# power_supply.net
KiCad netlist of a schematic drawn in EAGLE
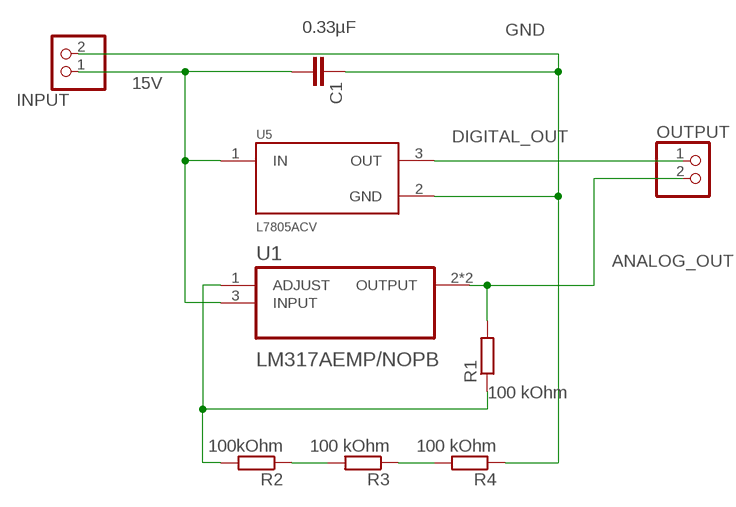
[diagram p0: schematic, sheet 1]

(export (version "E")
  (design (tool "Eeschema 10.0.6"))
  (components
    (comp (ref "C1")
      (value "0.33µF")
      (footprint "eagle-import:C0805")
      (libsource (lib "eagle-import") (part "C-EUC0805"))
    )
    (comp (ref "INPUT")
      (value "PINHD-1X2")
      (footprint "eagle-import:1X02")
      (libsource (lib "eagle-import") (part "PINHD-1X2"))
    )
    (comp (ref "OUTPUT")
      (value "PINHD-1X2")
      (footprint "eagle-import:1X02")
      (libsource (lib "eagle-import") (part "PINHD-1X2"))
    )
    (comp (ref "R1")
      (value "100 kOhm")
      (footprint "eagle-import:R0805")
      (libsource (lib "eagle-import") (part "R-EU_R0805"))
    )
    (comp (ref "R2")
      (value "100kOhm")
      (footprint "eagle-import:R0805")
      (libsource (lib "eagle-import") (part "R-EU_R0805"))
    )
    (comp (ref "R3")
      (value "100 kOhm")
      (footprint "eagle-import:R0805")
      (libsource (lib "eagle-import") (part "R-EU_R0805"))
    )
    (comp (ref "R4")
      (value "100 kOhm")
      (footprint "eagle-import:R0805")
      (libsource (lib "eagle-import") (part "R-EU_R0805"))
    )
    (comp (ref "U1")
      (value "LM317AEMP/NOPB")
      (footprint "eagle-import:SOT230P700X180-4N")
      (fields (field (name "MF") "Texas Instruments"))
      (libsource (lib "eagle-import") (part "LM317AEMP/NOPB"))
    )
    (comp (ref "U5")
      (value "L7805ACV")
      (footprint "eagle-import:TO254P460X1020X1945-3P")
      (fields (field (name "MF") "STMicroelectronics"))
      (libsource (lib "eagle-import") (part "L7805ACV"))
    )
  )
  (nets
    (net (code "1") (name "/15V") (class "Default")
      (node (ref "C1") (pin "2") (pinfunction "2_2") (pintype "passive"))
      (node (ref "INPUT") (pin "1") (pinfunction "1_1") (pintype "passive"))
      (node (ref "U1") (pin "3") (pinfunction "INPUT_3") (pintype "input"))
      (node (ref "U5") (pin "1") (pinfunction "IN_1") (pintype "input"))
    )
    (net (code "2") (name "/ANALOG_OUT") (class "Default")
      (node (ref "OUTPUT") (pin "2") (pinfunction "2_2") (pintype "passive"))
      (node (ref "R1") (pin "2") (pinfunction "2_2") (pintype "passive"))
      (node (ref "U1") (pin "2") (pinfunction "OUTPUT_2") (pintype "output"))
      (node (ref "U1") (pin "4") (pinfunction "OUTPUT_4") (pintype "output"))
    )
    (net (code "3") (name "/DIGITAL_OUT") (class "Default")
      (node (ref "OUTPUT") (pin "1") (pinfunction "1_1") (pintype "passive"))
      (node (ref "U5") (pin "3") (pinfunction "OUT_3") (pintype "output"))
    )
    (net (code "4") (name "/GND") (class "Default")
      (node (ref "C1") (pin "1") (pinfunction "1_1") (pintype "passive"))
      (node (ref "INPUT") (pin "2") (pinfunction "2_2") (pintype "passive"))
      (node (ref "R4") (pin "1") (pinfunction "1_1") (pintype "passive"))
      (node (ref "U5") (pin "2") (pinfunction "GND_2") (pintype "power_in"))
    )
    (net (code "5") (name "Net-(R2-Pad1)") (class "Default")
      (node (ref "R2") (pin "1") (pinfunction "1_1") (pintype "passive"))
      (node (ref "R3") (pin "2") (pinfunction "2_2") (pintype "passive"))
    )
    (net (code "6") (name "Net-(R3-Pad1)") (class "Default")
      (node (ref "R3") (pin "1") (pinfunction "1_1") (pintype "passive"))
      (node (ref "R4") (pin "2") (pinfunction "2_2") (pintype "passive"))
    )
    (net (code "7") (name "Net-(U1-ADJUST)") (class "Default")
      (node (ref "R1") (pin "1") (pinfunction "1_1") (pintype "passive"))
      (node (ref "R2") (pin "2") (pinfunction "2_2") (pintype "passive"))
      (node (ref "U1") (pin "1") (pinfunction "ADJUST_1") (pintype "input"))
    )
  )
)
